# bbb_light_2021-04-30.net
KiCad netlist of a schematic drawn in EAGLE
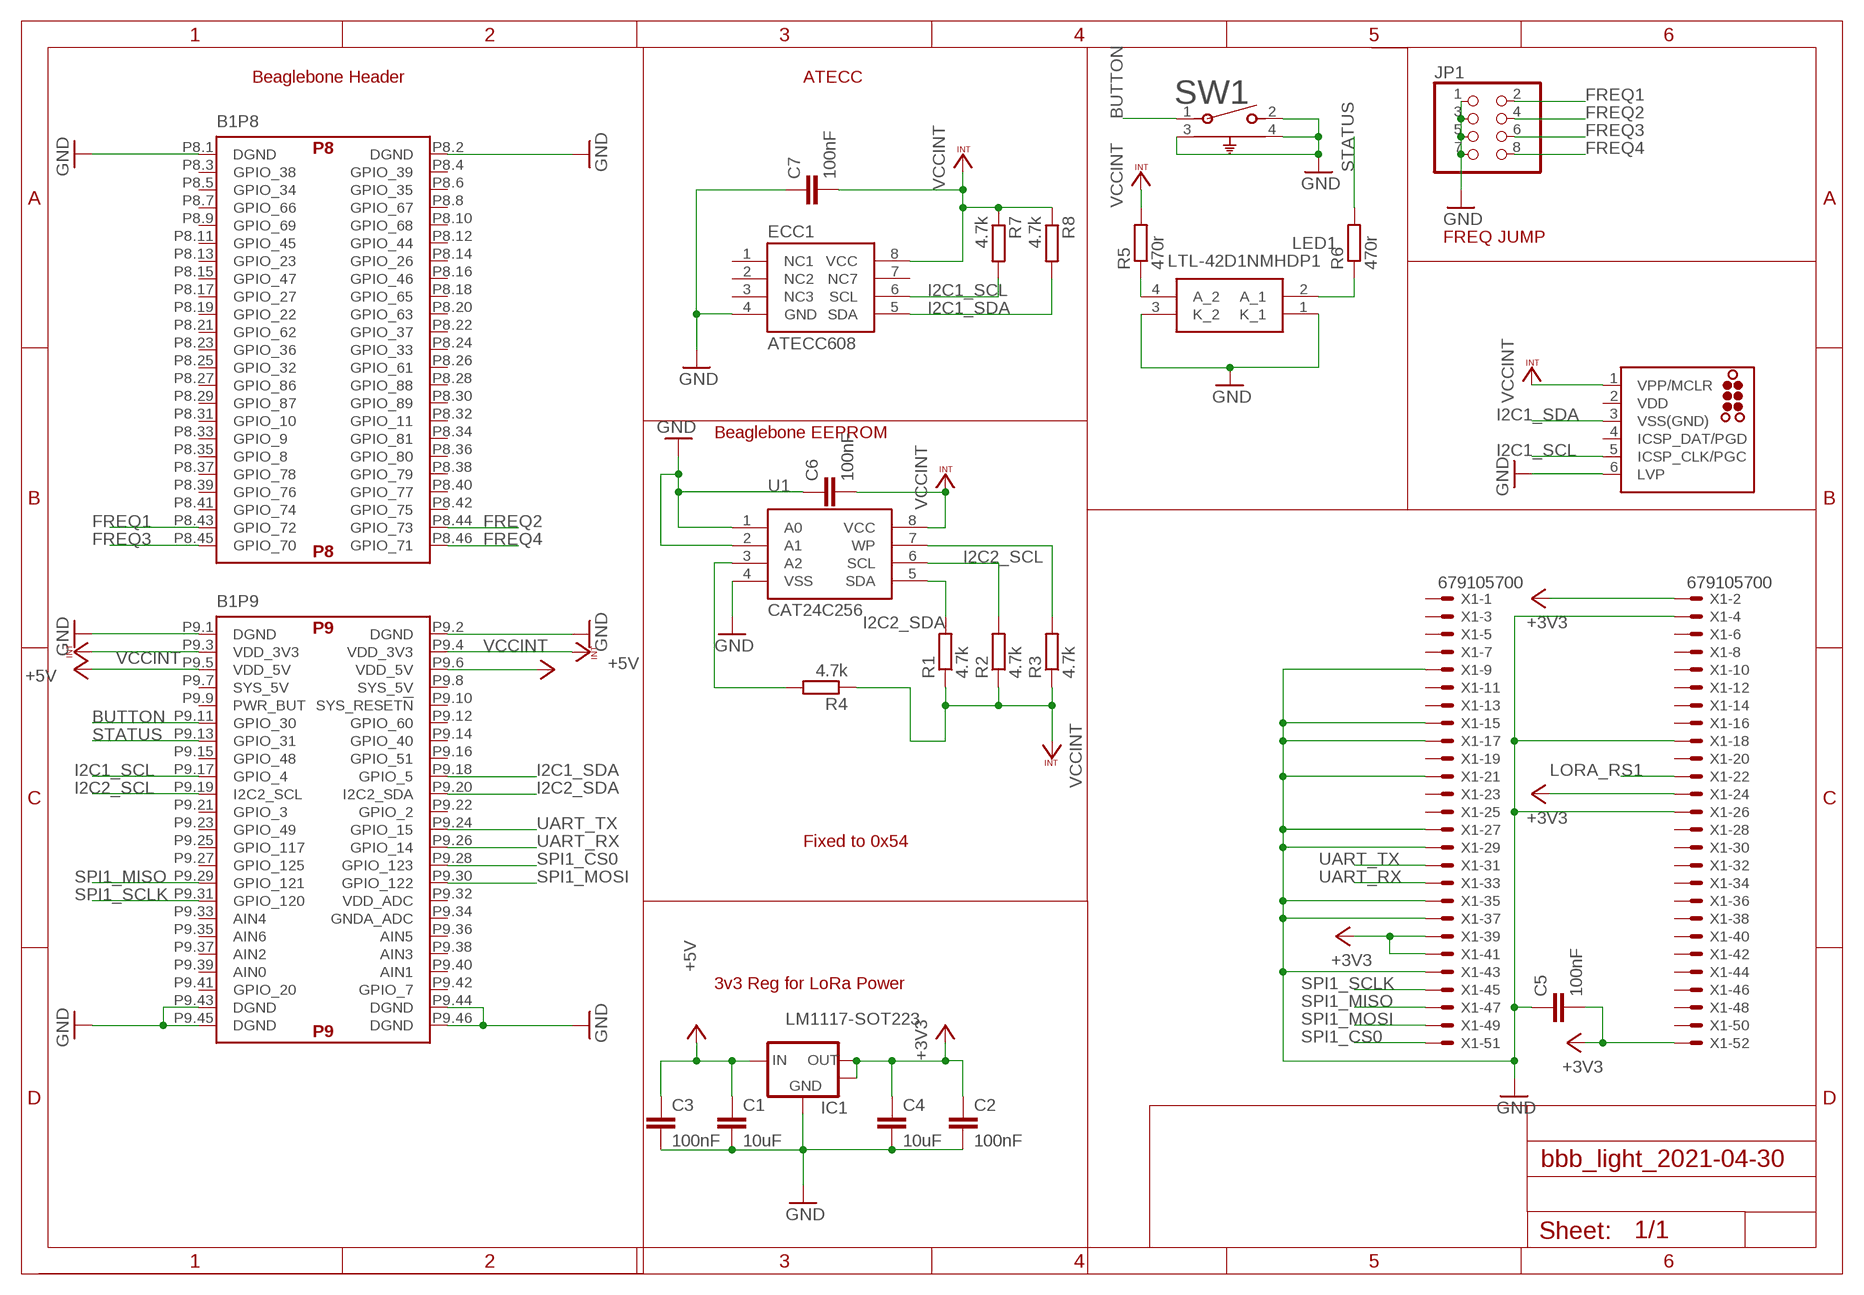
[diagram p0: schematic, sheet 1]

(export (version "E")
  (design (tool "Eeschema 10.0.6"))
  (components
    (comp (ref "B1")
      (value "SPARKFUN_BEAGLE_BONE_BLACK_CAPE")
      (footprint "eagle-import:BEAGLE_BONE_BLACK_CAPE")
      (libsource (lib "eagle-import") (part "SPARKFUN_BEAGLE_BONE_BLACK_CAPE"))
    )
    (comp (ref "C1")
      (value "10uF")
      (footprint "eagle-import:C0603")
      (libsource (lib "eagle-import") (part "C-EUC0603"))
    )
    (comp (ref "C2")
      (value "100nF")
      (footprint "eagle-import:C0603")
      (libsource (lib "eagle-import") (part "C-EUC0603"))
    )
    (comp (ref "C3")
      (value "100nF")
      (footprint "eagle-import:C0603")
      (libsource (lib "eagle-import") (part "C-EUC0603"))
    )
    (comp (ref "C4")
      (value "10uF")
      (footprint "eagle-import:C0603")
      (libsource (lib "eagle-import") (part "C-EUC0603"))
    )
    (comp (ref "C5")
      (value "100nF")
      (footprint "eagle-import:C0603")
      (libsource (lib "eagle-import") (part "C-EUC0603"))
    )
    (comp (ref "C6")
      (value "100nF")
      (footprint "eagle-import:C0603")
      (libsource (lib "eagle-import") (part "C-EUC0603"))
    )
    (comp (ref "C7")
      (value "100nF")
      (footprint "eagle-import:C0603")
      (libsource (lib "eagle-import") (part "C-EUC0603"))
    )
    (comp (ref "ECC1")
      (value "ATECC608")
      (footprint "eagle-import:SO08")
      (libsource (lib "eagle-import") (part "ATECC108"))
    )
    (comp (ref "IC1")
      (value "LM1117-SOT223")
      (footprint "eagle-import:SOT-223-3")
      (libsource (lib "eagle-import") (part "LM1117-SOT223"))
    )
    (comp (ref "J1")
      (value "TC2030-MCP-NL")
      (footprint "eagle-import:TC2030-MCP-NL")
      (libsource (lib "eagle-import") (part "TC2030-MCP-NL"))
    )
    (comp (ref "JP1")
      (value "PINHD-2X4")
      (footprint "eagle-import:2X04")
      (libsource (lib "eagle-import") (part "PINHD-2X4"))
    )
    (comp (ref "LED1")
      (value "LTL-42D1NMHDP1")
      (footprint "eagle-import:LTL42D1NMHDP1")
      (fields (field (name "MOUSER_PART_NUMBER") "859-LTL-42D1NMHDP1"))
      (libsource (lib "eagle-import") (part "LTL-42D1NMHDP1"))
    )
    (comp (ref "R1")
      (value "4.7k")
      (footprint "eagle-import:R0603")
      (libsource (lib "eagle-import") (part "R-EU_R0603"))
    )
    (comp (ref "R2")
      (value "4.7k")
      (footprint "eagle-import:R0603")
      (libsource (lib "eagle-import") (part "R-EU_R0603"))
    )
    (comp (ref "R3")
      (value "4.7k")
      (footprint "eagle-import:R0603")
      (libsource (lib "eagle-import") (part "R-EU_R0603"))
    )
    (comp (ref "R4")
      (value "4.7k")
      (footprint "eagle-import:R0603")
      (libsource (lib "eagle-import") (part "R-EU_R0603"))
    )
    (comp (ref "R5")
      (value "470r")
      (footprint "eagle-import:R0603")
      (libsource (lib "eagle-import") (part "R-EU_R0603"))
    )
    (comp (ref "R6")
      (value "470r")
      (footprint "eagle-import:R0603")
      (libsource (lib "eagle-import") (part "R-EU_R0603"))
    )
    (comp (ref "R7")
      (value "4.7k")
      (footprint "eagle-import:R0603")
      (libsource (lib "eagle-import") (part "R-EU_R0603"))
    )
    (comp (ref "R8")
      (value "4.7k")
      (footprint "eagle-import:R0603")
      (libsource (lib "eagle-import") (part "R-EU_R0603"))
    )
    (comp (ref "SW1")
      (value "1825027-8")
      (footprint "eagle-import:SW2_1825027-C_TEC")
      (fields (field (name "COPYRIGHT") "Copyright (C) 2016 Accelerated Designs. All rights reserved"))
      (libsource (lib "eagle-import") (part "1825027-8"))
    )
    (comp (ref "U1")
      (value "CAT24C256")
      (footprint "eagle-import:SOIC8")
      (fields
        (field (name "DIGIKEY_PART_NUMBER") "CAT24C32WI-GT3CT-ND")
        (field (name "MANUFACTURER") "ON Semiconductor")
        (field (name "MPN") "CAT24C32WI-GT3")
        (field (name "CREATED_BY") "PCBLayout.com")
      )
      (libsource (lib "eagle-import") (part "CAT24C32WI-GT3"))
    )
    (comp (ref "X1")
      (value "679105700")
      (footprint "eagle-import:679105700")
      (fields (field (name "MPN") "67910-5700"))
      (libsource (lib "eagle-import") (part "679105700"))
    )
  )
  (nets
    (net (code "1") (name "+3V3") (class "Default")
      (node (ref "C2") (pin "1") (pinfunction "1_1") (pintype "passive"))
      (node (ref "C4") (pin "1") (pinfunction "1_1") (pintype "passive"))
      (node (ref "C5") (pin "2") (pinfunction "2_2") (pintype "passive"))
      (node (ref "IC1") (pin "2") (pinfunction "VOUT_2") (pintype "bidirectional"))
      (node (ref "IC1") (pin "4") (pinfunction "HEATSINK_4") (pintype "bidirectional"))
      (node (ref "X1") (pin "2") (pinfunction "S_2") (pintype "passive"))
      (node (ref "X1") (pin "24") (pinfunction "S_24") (pintype "passive"))
      (node (ref "X1") (pin "39") (pinfunction "S_39") (pintype "passive"))
      (node (ref "X1") (pin "41") (pinfunction "S_41") (pintype "passive"))
      (node (ref "X1") (pin "52") (pinfunction "S_52") (pintype "passive"))
    )
    (net (code "2") (name "+5V") (class "Default")
      (node (ref "B1") (pin "P9.5") (pinfunction "VDD_5V_P9.5") (pintype "bidirectional"))
      (node (ref "B1") (pin "P9.6") (pinfunction "VDD_5V_P9.6") (pintype "bidirectional"))
      (node (ref "C1") (pin "1") (pinfunction "1_1") (pintype "passive"))
      (node (ref "C3") (pin "1") (pinfunction "1_1") (pintype "passive"))
      (node (ref "IC1") (pin "3") (pinfunction "VIN_3") (pintype "bidirectional"))
    )
    (net (code "3") (name "/BUTTON") (class "Default")
      (node (ref "B1") (pin "P9.11") (pinfunction "GPIO_30_P9.11") (pintype "bidirectional"))
      (node (ref "SW1") (pin "1") (pinfunction "1_1") (pintype "passive"))
    )
    (net (code "4") (name "/FREQ1") (class "Default")
      (node (ref "B1") (pin "P8.43") (pinfunction "GPIO_72_P8.43") (pintype "bidirectional"))
      (node (ref "JP1") (pin "2") (pinfunction "2_2") (pintype "passive"))
    )
    (net (code "5") (name "/FREQ2") (class "Default")
      (node (ref "B1") (pin "P8.44") (pinfunction "GPIO_73_P8.44") (pintype "bidirectional"))
      (node (ref "JP1") (pin "4") (pinfunction "4_4") (pintype "passive"))
    )
    (net (code "6") (name "/FREQ3") (class "Default")
      (node (ref "B1") (pin "P8.45") (pinfunction "GPIO_70_P8.45") (pintype "bidirectional"))
      (node (ref "JP1") (pin "6") (pinfunction "6_6") (pintype "passive"))
    )
    (net (code "7") (name "/FREQ4") (class "Default")
      (node (ref "B1") (pin "P8.46") (pinfunction "GPIO_71_P8.46") (pintype "bidirectional"))
      (node (ref "JP1") (pin "8") (pinfunction "8_8") (pintype "passive"))
    )
    (net (code "8") (name "/I2C1_SCL") (class "Default")
      (node (ref "B1") (pin "P9.17") (pinfunction "GPIO_4_P9.17") (pintype "bidirectional"))
      (node (ref "ECC1") (pin "6") (pinfunction "SCL_6") (pintype "bidirectional"))
      (node (ref "J1") (pin "5") (pinfunction "ICSP_CLK/PGC_5") (pintype "output"))
      (node (ref "R7") (pin "2") (pinfunction "2_2") (pintype "passive"))
    )
    (net (code "9") (name "/I2C1_SDA") (class "Default")
      (node (ref "B1") (pin "P9.18") (pinfunction "GPIO_5_P9.18") (pintype "bidirectional"))
      (node (ref "ECC1") (pin "5") (pinfunction "SDA_5") (pintype "bidirectional"))
      (node (ref "J1") (pin "3") (pinfunction "VSS(GND)_3") (pintype "power_in"))
      (node (ref "R8") (pin "2") (pinfunction "2_2") (pintype "passive"))
    )
    (net (code "10") (name "/I2C2_SCL") (class "Default")
      (node (ref "B1") (pin "P9.19") (pinfunction "I2C2_SCL_P9.19") (pintype "bidirectional"))
      (node (ref "R2") (pin "2") (pinfunction "2_2") (pintype "passive"))
      (node (ref "U1") (pin "6") (pinfunction "SCL_6") (pintype "input"))
    )
    (net (code "11") (name "/I2C2_SDA") (class "Default")
      (node (ref "B1") (pin "P9.20") (pinfunction "I2C2_SDA_P9.20") (pintype "bidirectional"))
      (node (ref "R1") (pin "2") (pinfunction "2_2") (pintype "passive"))
      (node (ref "U1") (pin "5") (pinfunction "SDA_5") (pintype "bidirectional"))
    )
    (net (code "12") (name "/LORA_RS1") (class "Default")
      (node (ref "X1") (pin "22") (pinfunction "S_22") (pintype "passive"))
    )
    (net (code "13") (name "/SPI1_CS0") (class "Default")
      (node (ref "B1") (pin "P9.28") (pinfunction "GPIO_123_P9.28") (pintype "bidirectional"))
      (node (ref "X1") (pin "51") (pinfunction "S_51") (pintype "passive"))
    )
    (net (code "14") (name "/SPI1_MISO") (class "Default")
      (node (ref "B1") (pin "P9.29") (pinfunction "GPIO_121_P9.29") (pintype "bidirectional"))
      (node (ref "X1") (pin "47") (pinfunction "S_47") (pintype "passive"))
    )
    (net (code "15") (name "/SPI1_MOSI") (class "Default")
      (node (ref "B1") (pin "P9.30") (pinfunction "GPIO_122_P9.30") (pintype "bidirectional"))
      (node (ref "X1") (pin "49") (pinfunction "S_49") (pintype "passive"))
    )
    (net (code "16") (name "/SPI1_SCLK") (class "Default")
      (node (ref "B1") (pin "P9.31") (pinfunction "GPIO_120_P9.31") (pintype "bidirectional"))
      (node (ref "X1") (pin "45") (pinfunction "S_45") (pintype "passive"))
    )
    (net (code "17") (name "/STATUS") (class "Default")
      (node (ref "B1") (pin "P9.13") (pinfunction "GPIO_31_P9.13") (pintype "bidirectional"))
      (node (ref "R6") (pin "2") (pinfunction "2_2") (pintype "passive"))
    )
    (net (code "18") (name "/UART_RX") (class "Default")
      (node (ref "B1") (pin "P9.26") (pinfunction "GPIO_14_P9.26") (pintype "bidirectional"))
      (node (ref "X1") (pin "33") (pinfunction "S_33") (pintype "passive"))
    )
    (net (code "19") (name "/UART_TX") (class "Default")
      (node (ref "B1") (pin "P9.24") (pinfunction "GPIO_15_P9.24") (pintype "bidirectional"))
      (node (ref "X1") (pin "31") (pinfunction "S_31") (pintype "passive"))
    )
    (net (code "20") (name "/VDD") (class "Default")
      (node (ref "J1") (pin "2") (pinfunction "VDD_2") (pintype "power_in"))
    )
    (net (code "21") (name "GND") (class "Default")
      (node (ref "B1") (pin "P8.1") (pinfunction "DGND_P8.1") (pintype "bidirectional"))
      (node (ref "B1") (pin "P8.2") (pinfunction "DGND_P8.2") (pintype "bidirectional"))
      (node (ref "B1") (pin "P9.1") (pinfunction "DGND_P9.1") (pintype "bidirectional"))
      (node (ref "B1") (pin "P9.2") (pinfunction "DGND_P9.2") (pintype "bidirectional"))
      (node (ref "B1") (pin "P9.43") (pinfunction "DGND_P9.43") (pintype "bidirectional"))
      (node (ref "B1") (pin "P9.44") (pinfunction "DGND_P9.44") (pintype "bidirectional"))
      (node (ref "B1") (pin "P9.45") (pinfunction "DGND_P9.45") (pintype "bidirectional"))
      (node (ref "B1") (pin "P9.46") (pinfunction "DGND_P9.46") (pintype "bidirectional"))
      (node (ref "C1") (pin "2") (pinfunction "2_2") (pintype "passive"))
      (node (ref "C2") (pin "2") (pinfunction "2_2") (pintype "passive"))
      (node (ref "C3") (pin "2") (pinfunction "2_2") (pintype "passive"))
      (node (ref "C4") (pin "2") (pinfunction "2_2") (pintype "passive"))
      (node (ref "C5") (pin "1") (pinfunction "1_1") (pintype "passive"))
      (node (ref "C6") (pin "1") (pinfunction "1_1") (pintype "passive"))
      (node (ref "C7") (pin "1") (pinfunction "1_1") (pintype "passive"))
      (node (ref "ECC1") (pin "4") (pinfunction "GND_4") (pintype "power_in"))
      (node (ref "IC1") (pin "1") (pinfunction "GND_1") (pintype "bidirectional"))
      (node (ref "J1") (pin "6") (pinfunction "LVP_6") (pintype "bidirectional"))
      (node (ref "JP1") (pin "1") (pinfunction "1_1") (pintype "passive"))
      (node (ref "JP1") (pin "3") (pinfunction "3_3") (pintype "passive"))
      (node (ref "JP1") (pin "5") (pinfunction "5_5") (pintype "passive"))
      (node (ref "JP1") (pin "7") (pinfunction "7_7") (pintype "passive"))
      (node (ref "LED1") (pin "1") (pinfunction "K_1_1") (pintype "bidirectional"))
      (node (ref "LED1") (pin "3") (pinfunction "K_2_3") (pintype "bidirectional"))
      (node (ref "SW1") (pin "2") (pinfunction "2_2") (pintype "passive"))
      (node (ref "SW1") (pin "3") (pinfunction "3_3") (pintype "passive"))
      (node (ref "SW1") (pin "4") (pinfunction "4_4") (pintype "passive"))
      (node (ref "U1") (pin "1") (pinfunction "A0_1") (pintype "input"))
      (node (ref "U1") (pin "2") (pinfunction "A1_2") (pintype "input"))
      (node (ref "U1") (pin "4") (pinfunction "VSS_4") (pintype "power_in"))
      (node (ref "X1") (pin "15") (pinfunction "S_15") (pintype "passive"))
      (node (ref "X1") (pin "17") (pinfunction "S_17") (pintype "passive"))
      (node (ref "X1") (pin "18") (pinfunction "S_18") (pintype "passive"))
      (node (ref "X1") (pin "21") (pinfunction "S_21") (pintype "passive"))
      (node (ref "X1") (pin "26") (pinfunction "S_26") (pintype "passive"))
      (node (ref "X1") (pin "27") (pinfunction "S_27") (pintype "passive"))
      (node (ref "X1") (pin "29") (pinfunction "S_29") (pintype "passive"))
      (node (ref "X1") (pin "35") (pinfunction "S_35") (pintype "passive"))
      (node (ref "X1") (pin "37") (pinfunction "S_37") (pintype "passive"))
      (node (ref "X1") (pin "4") (pinfunction "S_4") (pintype "passive"))
      (node (ref "X1") (pin "43") (pinfunction "S_43") (pintype "passive"))
      (node (ref "X1") (pin "9") (pinfunction "S_9") (pintype "passive"))
    )
    (net (code "22") (name "Net-(LED1-A_1)") (class "Default")
      (node (ref "LED1") (pin "2") (pinfunction "A_1_2") (pintype "bidirectional"))
      (node (ref "R6") (pin "1") (pinfunction "1_1") (pintype "passive"))
    )
    (net (code "23") (name "Net-(LED1-A_2)") (class "Default")
      (node (ref "LED1") (pin "4") (pinfunction "A_2_4") (pintype "bidirectional"))
      (node (ref "R5") (pin "1") (pinfunction "1_1") (pintype "passive"))
    )
    (net (code "24") (name "Net-(U1-A2)") (class "Default")
      (node (ref "R4") (pin "2") (pinfunction "2_2") (pintype "passive"))
      (node (ref "U1") (pin "3") (pinfunction "A2_3") (pintype "input"))
    )
    (net (code "25") (name "Net-(U1-WP)") (class "Default")
      (node (ref "R3") (pin "2") (pinfunction "2_2") (pintype "passive"))
      (node (ref "U1") (pin "7") (pinfunction "WP_7") (pintype "input"))
    )
    (net (code "26") (name "VCCINT") (class "Default")
      (node (ref "B1") (pin "P9.3") (pinfunction "VDD_3V3_P9.3") (pintype "bidirectional"))
      (node (ref "B1") (pin "P9.4") (pinfunction "VDD_3V3_P9.4") (pintype "bidirectional"))
      (node (ref "C6") (pin "2") (pinfunction "2_2") (pintype "passive"))
      (node (ref "C7") (pin "2") (pinfunction "2_2") (pintype "passive"))
      (node (ref "ECC1") (pin "8") (pinfunction "VCC_8") (pintype "power_in"))
      (node (ref "J1") (pin "1") (pinfunction "VPP/MCLR_1") (pintype "passive"))
      (node (ref "R1") (pin "1") (pinfunction "1_1") (pintype "passive"))
      (node (ref "R2") (pin "1") (pinfunction "1_1") (pintype "passive"))
      (node (ref "R3") (pin "1") (pinfunction "1_1") (pintype "passive"))
      (node (ref "R4") (pin "1") (pinfunction "1_1") (pintype "passive"))
      (node (ref "R5") (pin "2") (pinfunction "2_2") (pintype "passive"))
      (node (ref "R7") (pin "1") (pinfunction "1_1") (pintype "passive"))
      (node (ref "R8") (pin "1") (pinfunction "1_1") (pintype "passive"))
      (node (ref "U1") (pin "8") (pinfunction "VCC_8") (pintype "power_in"))
    )
    (net (code "27") (name "unconnected-(B1A-GPIO_8-PadP8.35)") (class "Default")
      (node (ref "B1") (pin "P8.35") (pinfunction "GPIO_8_P8.35") (pintype "bidirectional"))
    )
    (net (code "28") (name "unconnected-(B1A-GPIO_9-PadP8.33)") (class "Default")
      (node (ref "B1") (pin "P8.33") (pinfunction "GPIO_9_P8.33") (pintype "bidirectional"))
    )
    (net (code "29") (name "unconnected-(B1A-GPIO_10-PadP8.31)") (class "Default")
      (node (ref "B1") (pin "P8.31") (pinfunction "GPIO_10_P8.31") (pintype "bidirectional"))
    )
    (net (code "30") (name "unconnected-(B1A-GPIO_11-PadP8.32)") (class "Default")
      (node (ref "B1") (pin "P8.32") (pinfunction "GPIO_11_P8.32") (pintype "bidirectional"))
    )
    (net (code "31") (name "unconnected-(B1A-GPIO_22-PadP8.19)") (class "Default")
      (node (ref "B1") (pin "P8.19") (pinfunction "GPIO_22_P8.19") (pintype "bidirectional"))
    )
    (net (code "32") (name "unconnected-(B1A-GPIO_23-PadP8.13)") (class "Default")
      (node (ref "B1") (pin "P8.13") (pinfunction "GPIO_23_P8.13") (pintype "bidirectional"))
    )
    (net (code "33") (name "unconnected-(B1A-GPIO_26-PadP8.14)") (class "Default")
      (node (ref "B1") (pin "P8.14") (pinfunction "GPIO_26_P8.14") (pintype "bidirectional"))
    )
    (net (code "34") (name "unconnected-(B1A-GPIO_27-PadP8.17)") (class "Default")
      (node (ref "B1") (pin "P8.17") (pinfunction "GPIO_27_P8.17") (pintype "bidirectional"))
    )
    (net (code "35") (name "unconnected-(B1A-GPIO_32-PadP8.25)") (class "Default")
      (node (ref "B1") (pin "P8.25") (pinfunction "GPIO_32_P8.25") (pintype "bidirectional"))
    )
    (net (code "36") (name "unconnected-(B1A-GPIO_33-PadP8.24)") (class "Default")
      (node (ref "B1") (pin "P8.24") (pinfunction "GPIO_33_P8.24") (pintype "bidirectional"))
    )
    (net (code "37") (name "unconnected-(B1A-GPIO_34-PadP8.5)") (class "Default")
      (node (ref "B1") (pin "P8.5") (pinfunction "GPIO_34_P8.5") (pintype "bidirectional"))
    )
    (net (code "38") (name "unconnected-(B1A-GPIO_35-PadP8.6)") (class "Default")
      (node (ref "B1") (pin "P8.6") (pinfunction "GPIO_35_P8.6") (pintype "bidirectional"))
    )
    (net (code "39") (name "unconnected-(B1A-GPIO_36-PadP8.23)") (class "Default")
      (node (ref "B1") (pin "P8.23") (pinfunction "GPIO_36_P8.23") (pintype "bidirectional"))
    )
    (net (code "40") (name "unconnected-(B1A-GPIO_37-PadP8.22)") (class "Default")
      (node (ref "B1") (pin "P8.22") (pinfunction "GPIO_37_P8.22") (pintype "bidirectional"))
    )
    (net (code "41") (name "unconnected-(B1A-GPIO_38-PadP8.3)") (class "Default")
      (node (ref "B1") (pin "P8.3") (pinfunction "GPIO_38_P8.3") (pintype "bidirectional"))
    )
    (net (code "42") (name "unconnected-(B1A-GPIO_39-PadP8.4)") (class "Default")
      (node (ref "B1") (pin "P8.4") (pinfunction "GPIO_39_P8.4") (pintype "bidirectional"))
    )
    (net (code "43") (name "unconnected-(B1A-GPIO_44-PadP8.12)") (class "Default")
      (node (ref "B1") (pin "P8.12") (pinfunction "GPIO_44_P8.12") (pintype "bidirectional"))
    )
    (net (code "44") (name "unconnected-(B1A-GPIO_45-PadP8.11)") (class "Default")
      (node (ref "B1") (pin "P8.11") (pinfunction "GPIO_45_P8.11") (pintype "bidirectional"))
    )
    (net (code "45") (name "unconnected-(B1A-GPIO_46-PadP8.16)") (class "Default")
      (node (ref "B1") (pin "P8.16") (pinfunction "GPIO_46_P8.16") (pintype "bidirectional"))
    )
    (net (code "46") (name "unconnected-(B1A-GPIO_47-PadP8.15)") (class "Default")
      (node (ref "B1") (pin "P8.15") (pinfunction "GPIO_47_P8.15") (pintype "bidirectional"))
    )
    (net (code "47") (name "unconnected-(B1A-GPIO_61-PadP8.26)") (class "Default")
      (node (ref "B1") (pin "P8.26") (pinfunction "GPIO_61_P8.26") (pintype "bidirectional"))
    )
    (net (code "48") (name "unconnected-(B1A-GPIO_62-PadP8.21)") (class "Default")
      (node (ref "B1") (pin "P8.21") (pinfunction "GPIO_62_P8.21") (pintype "bidirectional"))
    )
    (net (code "49") (name "unconnected-(B1A-GPIO_63-PadP8.20)") (class "Default")
      (node (ref "B1") (pin "P8.20") (pinfunction "GPIO_63_P8.20") (pintype "bidirectional"))
    )
    (net (code "50") (name "unconnected-(B1A-GPIO_65-PadP8.18)") (class "Default")
      (node (ref "B1") (pin "P8.18") (pinfunction "GPIO_65_P8.18") (pintype "bidirectional"))
    )
    (net (code "51") (name "unconnected-(B1A-GPIO_66-PadP8.7)") (class "Default")
      (node (ref "B1") (pin "P8.7") (pinfunction "GPIO_66_P8.7") (pintype "bidirectional"))
    )
    (net (code "52") (name "unconnected-(B1A-GPIO_67-PadP8.8)") (class "Default")
      (node (ref "B1") (pin "P8.8") (pinfunction "GPIO_67_P8.8") (pintype "bidirectional"))
    )
    (net (code "53") (name "unconnected-(B1A-GPIO_68-PadP8.10)") (class "Default")
      (node (ref "B1") (pin "P8.10") (pinfunction "GPIO_68_P8.10") (pintype "bidirectional"))
    )
    (net (code "54") (name "unconnected-(B1A-GPIO_69-PadP8.9)") (class "Default")
      (node (ref "B1") (pin "P8.9") (pinfunction "GPIO_69_P8.9") (pintype "bidirectional"))
    )
    (net (code "55") (name "unconnected-(B1A-GPIO_74-PadP8.41)") (class "Default")
      (node (ref "B1") (pin "P8.41") (pinfunction "GPIO_74_P8.41") (pintype "bidirectional"))
    )
    (net (code "56") (name "unconnected-(B1A-GPIO_75-PadP8.42)") (class "Default")
      (node (ref "B1") (pin "P8.42") (pinfunction "GPIO_75_P8.42") (pintype "bidirectional"))
    )
    (net (code "57") (name "unconnected-(B1A-GPIO_76-PadP8.39)") (class "Default")
      (node (ref "B1") (pin "P8.39") (pinfunction "GPIO_76_P8.39") (pintype "bidirectional"))
    )
    (net (code "58") (name "unconnected-(B1A-GPIO_77-PadP8.40)") (class "Default")
      (node (ref "B1") (pin "P8.40") (pinfunction "GPIO_77_P8.40") (pintype "bidirectional"))
    )
    (net (code "59") (name "unconnected-(B1A-GPIO_78-PadP8.37)") (class "Default")
      (node (ref "B1") (pin "P8.37") (pinfunction "GPIO_78_P8.37") (pintype "bidirectional"))
    )
    (net (code "60") (name "unconnected-(B1A-GPIO_79-PadP8.38)") (class "Default")
      (node (ref "B1") (pin "P8.38") (pinfunction "GPIO_79_P8.38") (pintype "bidirectional"))
    )
    (net (code "61") (name "unconnected-(B1A-GPIO_80-PadP8.36)") (class "Default")
      (node (ref "B1") (pin "P8.36") (pinfunction "GPIO_80_P8.36") (pintype "bidirectional"))
    )
    (net (code "62") (name "unconnected-(B1A-GPIO_81-PadP8.34)") (class "Default")
      (node (ref "B1") (pin "P8.34") (pinfunction "GPIO_81_P8.34") (pintype "bidirectional"))
    )
    (net (code "63") (name "unconnected-(B1A-GPIO_86-PadP8.27)") (class "Default")
      (node (ref "B1") (pin "P8.27") (pinfunction "GPIO_86_P8.27") (pintype "bidirectional"))
    )
    (net (code "64") (name "unconnected-(B1A-GPIO_87-PadP8.29)") (class "Default")
      (node (ref "B1") (pin "P8.29") (pinfunction "GPIO_87_P8.29") (pintype "bidirectional"))
    )
    (net (code "65") (name "unconnected-(B1A-GPIO_88-PadP8.28)") (class "Default")
      (node (ref "B1") (pin "P8.28") (pinfunction "GPIO_88_P8.28") (pintype "bidirectional"))
    )
    (net (code "66") (name "unconnected-(B1A-GPIO_89-PadP8.30)") (class "Default")
      (node (ref "B1") (pin "P8.30") (pinfunction "GPIO_89_P8.30") (pintype "bidirectional"))
    )
    (net (code "67") (name "unconnected-(B1B-AIN0-PadP9.39)") (class "Default")
      (node (ref "B1") (pin "P9.39") (pinfunction "AIN0_P9.39") (pintype "bidirectional"))
    )
    (net (code "68") (name "unconnected-(B1B-AIN1-PadP9.40)") (class "Default")
      (node (ref "B1") (pin "P9.40") (pinfunction "AIN1_P9.40") (pintype "bidirectional"))
    )
    (net (code "69") (name "unconnected-(B1B-AIN2-PadP9.37)") (class "Default")
      (node (ref "B1") (pin "P9.37") (pinfunction "AIN2_P9.37") (pintype "bidirectional"))
    )
    (net (code "70") (name "unconnected-(B1B-AIN3-PadP9.38)") (class "Default")
      (node (ref "B1") (pin "P9.38") (pinfunction "AIN3_P9.38") (pintype "bidirectional"))
    )
    (net (code "71") (name "unconnected-(B1B-AIN4-PadP9.33)") (class "Default")
      (node (ref "B1") (pin "P9.33") (pinfunction "AIN4_P9.33") (pintype "bidirectional"))
    )
    (net (code "72") (name "unconnected-(B1B-AIN5-PadP9.36)") (class "Default")
      (node (ref "B1") (pin "P9.36") (pinfunction "AIN5_P9.36") (pintype "bidirectional"))
    )
    (net (code "73") (name "unconnected-(B1B-AIN6-PadP9.35)") (class "Default")
      (node (ref "B1") (pin "P9.35") (pinfunction "AIN6_P9.35") (pintype "bidirectional"))
    )
    (net (code "74") (name "unconnected-(B1B-GNDA_ADC-PadP9.34)") (class "Default")
      (node (ref "B1") (pin "P9.34") (pinfunction "GNDA_ADC_P9.34") (pintype "bidirectional"))
    )
    (net (code "75") (name "unconnected-(B1B-GPIO_2-PadP9.22)") (class "Default")
      (node (ref "B1") (pin "P9.22") (pinfunction "GPIO_2_P9.22") (pintype "bidirectional"))
    )
    (net (code "76") (name "unconnected-(B1B-GPIO_3-PadP9.21)") (class "Default")
      (node (ref "B1") (pin "P9.21") (pinfunction "GPIO_3_P9.21") (pintype "bidirectional"))
    )
    (net (code "77") (name "unconnected-(B1B-GPIO_7-PadP9.42)") (class "Default")
      (node (ref "B1") (pin "P9.42") (pinfunction "GPIO_7_P9.42") (pintype "bidirectional"))
    )
    (net (code "78") (name "unconnected-(B1B-GPIO_20-PadP9.41)") (class "Default")
      (node (ref "B1") (pin "P9.41") (pinfunction "GPIO_20_P9.41") (pintype "bidirectional"))
    )
    (net (code "79") (name "unconnected-(B1B-GPIO_40-PadP9.14)") (class "Default")
      (node (ref "B1") (pin "P9.14") (pinfunction "GPIO_40_P9.14") (pintype "bidirectional"))
    )
    (net (code "80") (name "unconnected-(B1B-GPIO_48-PadP9.15)") (class "Default")
      (node (ref "B1") (pin "P9.15") (pinfunction "GPIO_48_P9.15") (pintype "bidirectional"))
    )
    (net (code "81") (name "unconnected-(B1B-GPIO_49-PadP9.23)") (class "Default")
      (node (ref "B1") (pin "P9.23") (pinfunction "GPIO_49_P9.23") (pintype "bidirectional"))
    )
    (net (code "82") (name "unconnected-(B1B-GPIO_51-PadP9.16)") (class "Default")
      (node (ref "B1") (pin "P9.16") (pinfunction "GPIO_51_P9.16") (pintype "bidirectional"))
    )
    (net (code "83") (name "unconnected-(B1B-GPIO_60-PadP9.12)") (class "Default")
      (node (ref "B1") (pin "P9.12") (pinfunction "GPIO_60_P9.12") (pintype "bidirectional"))
    )
    (net (code "84") (name "unconnected-(B1B-GPIO_117-PadP9.25)") (class "Default")
      (node (ref "B1") (pin "P9.25") (pinfunction "GPIO_117_P9.25") (pintype "bidirectional"))
    )
    (net (code "85") (name "unconnected-(B1B-GPIO_125-PadP9.27)") (class "Default")
      (node (ref "B1") (pin "P9.27") (pinfunction "GPIO_125_P9.27") (pintype "bidirectional"))
    )
    (net (code "86") (name "unconnected-(B1B-PWR_BUT-PadP9.9)") (class "Default")
      (node (ref "B1") (pin "P9.9") (pinfunction "PWR_BUT_P9.9") (pintype "bidirectional"))
    )
    (net (code "87") (name "unconnected-(B1B-SYS_5V-PadP9.7)") (class "Default")
      (node (ref "B1") (pin "P9.7") (pinfunction "SYS_5V_P9.7") (pintype "bidirectional"))
    )
    (net (code "88") (name "unconnected-(B1B-SYS_5V-PadP9.8)") (class "Default")
      (node (ref "B1") (pin "P9.8") (pinfunction "SYS_5V_P9.8") (pintype "bidirectional"))
    )
    (net (code "89") (name "unconnected-(B1B-SYS_RESET~{N}-PadP9.10)") (class "Default")
      (node (ref "B1") (pin "P9.10") (pinfunction "SYS_RESET~{N}_P9.10") (pintype "bidirectional"))
    )
    (net (code "90") (name "unconnected-(B1B-VDD_ADC-PadP9.32)") (class "Default")
      (node (ref "B1") (pin "P9.32") (pinfunction "VDD_ADC_P9.32") (pintype "bidirectional"))
    )
    (net (code "91") (name "unconnected-(ECC1-NC1-Pad1)") (class "Default")
      (node (ref "ECC1") (pin "1") (pinfunction "NC1_1") (pintype "bidirectional"))
    )
    (net (code "92") (name "unconnected-(ECC1-NC2-Pad2)") (class "Default")
      (node (ref "ECC1") (pin "2") (pinfunction "NC2_2") (pintype "no_connect"))
    )
    (net (code "93") (name "unconnected-(ECC1-NC3-Pad3)") (class "Default")
      (node (ref "ECC1") (pin "3") (pinfunction "NC3_3") (pintype "no_connect"))
    )
    (net (code "94") (name "unconnected-(ECC1-NC7-Pad7)") (class "Default")
      (node (ref "ECC1") (pin "7") (pinfunction "NC7_7") (pintype "no_connect"))
    )
    (net (code "95") (name "unconnected-(J1-ICSP_DAT{slash}PGD-Pad4)") (class "Default")
      (node (ref "J1") (pin "4") (pinfunction "ICSP_DAT/PGD_4") (pintype "bidirectional"))
    )
    (net (code "96") (name "unconnected-(X1A-S-Pad1)") (class "Default")
      (node (ref "X1") (pin "1") (pinfunction "S_1") (pintype "passive"))
    )
    (net (code "97") (name "unconnected-(X1AB-S-Pad34)") (class "Default")
      (node (ref "X1") (pin "34") (pinfunction "S_34") (pintype "passive"))
    )
    (net (code "98") (name "unconnected-(X1AD-S-Pad36)") (class "Default")
      (node (ref "X1") (pin "36") (pinfunction "S_36") (pintype "passive"))
    )
    (net (code "99") (name "unconnected-(X1AF-S-Pad38)") (class "Default")
      (node (ref "X1") (pin "38") (pinfunction "S_38") (pintype "passive"))
    )
    (net (code "100") (name "unconnected-(X1AI-S-Pad40)") (class "Default")
      (node (ref "X1") (pin "40") (pinfunction "S_40") (pintype "passive"))
    )
    (net (code "101") (name "unconnected-(X1AK-S-Pad42)") (class "Default")
      (node (ref "X1") (pin "42") (pinfunction "S_42") (pintype "passive"))
    )
    (net (code "102") (name "unconnected-(X1AM-S-Pad44)") (class "Default")
      (node (ref "X1") (pin "44") (pinfunction "S_44") (pintype "passive"))
    )
    (net (code "103") (name "unconnected-(X1AO-S-Pad46)") (class "Default")
      (node (ref "X1") (pin "46") (pinfunction "S_46") (pintype "passive"))
    )
    (net (code "104") (name "unconnected-(X1AQ-S-Pad48)") (class "Default")
      (node (ref "X1") (pin "48") (pinfunction "S_48") (pintype "passive"))
    )
    (net (code "105") (name "unconnected-(X1AS-S-Pad5)") (class "Default")
      (node (ref "X1") (pin "5") (pinfunction "S_5") (pintype "passive"))
    )
    (net (code "106") (name "unconnected-(X1AT-S-Pad50)") (class "Default")
      (node (ref "X1") (pin "50") (pinfunction "S_50") (pintype "passive"))
    )
    (net (code "107") (name "unconnected-(X1AW-S-Pad6)") (class "Default")
      (node (ref "X1") (pin "6") (pinfunction "S_6") (pintype "passive"))
    )
    (net (code "108") (name "unconnected-(X1AX-S-Pad7)") (class "Default")
      (node (ref "X1") (pin "7") (pinfunction "S_7") (pintype "passive"))
    )
    (net (code "109") (name "unconnected-(X1AY-S-Pad8)") (class "Default")
      (node (ref "X1") (pin "8") (pinfunction "S_8") (pintype "passive"))
    )
    (net (code "110") (name "unconnected-(X1B-S-Pad10)") (class "Default")
      (node (ref "X1") (pin "10") (pinfunction "S_10") (pintype "passive"))
    )
    (net (code "111") (name "unconnected-(X1C-S-Pad11)") (class "Default")
      (node (ref "X1") (pin "11") (pinfunction "S_11") (pintype "passive"))
    )
    (net (code "112") (name "unconnected-(X1D-S-Pad12)") (class "Default")
      (node (ref "X1") (pin "12") (pinfunction "S_12") (pintype "passive"))
    )
    (net (code "113") (name "unconnected-(X1E-S-Pad13)") (class "Default")
      (node (ref "X1") (pin "13") (pinfunction "S_13") (pintype "passive"))
    )
    (net (code "114") (name "unconnected-(X1F-S-Pad14)") (class "Default")
      (node (ref "X1") (pin "14") (pinfunction "S_14") (pintype "passive"))
    )
    (net (code "115") (name "unconnected-(X1H-S-Pad16)") (class "Default")
      (node (ref "X1") (pin "16") (pinfunction "S_16") (pintype "passive"))
    )
    (net (code "116") (name "unconnected-(X1K-S-Pad19)") (class "Default")
      (node (ref "X1") (pin "19") (pinfunction "S_19") (pintype "passive"))
    )
    (net (code "117") (name "unconnected-(X1M-S-Pad20)") (class "Default")
      (node (ref "X1") (pin "20") (pinfunction "S_20") (pintype "passive"))
    )
    (net (code "118") (name "unconnected-(X1P-S-Pad23)") (class "Default")
      (node (ref "X1") (pin "23") (pinfunction "S_23") (pintype "passive"))
    )
    (net (code "119") (name "unconnected-(X1R-S-Pad25)") (class "Default")
      (node (ref "X1") (pin "25") (pinfunction "S_25") (pintype "passive"))
    )
    (net (code "120") (name "unconnected-(X1U-S-Pad28)") (class "Default")
      (node (ref "X1") (pin "28") (pinfunction "S_28") (pintype "passive"))
    )
    (net (code "121") (name "unconnected-(X1W-S-Pad3)") (class "Default")
      (node (ref "X1") (pin "3") (pinfunction "S_3") (pintype "passive"))
    )
    (net (code "122") (name "unconnected-(X1X-S-Pad30)") (class "Default")
      (node (ref "X1") (pin "30") (pinfunction "S_30") (pintype "passive"))
    )
    (net (code "123") (name "unconnected-(X1Z-S-Pad32)") (class "Default")
      (node (ref "X1") (pin "32") (pinfunction "S_32") (pintype "passive"))
    )
  )
)
